# SD_CARD_REV2.net
KiCad netlist of a schematic drawn in Altium Designer
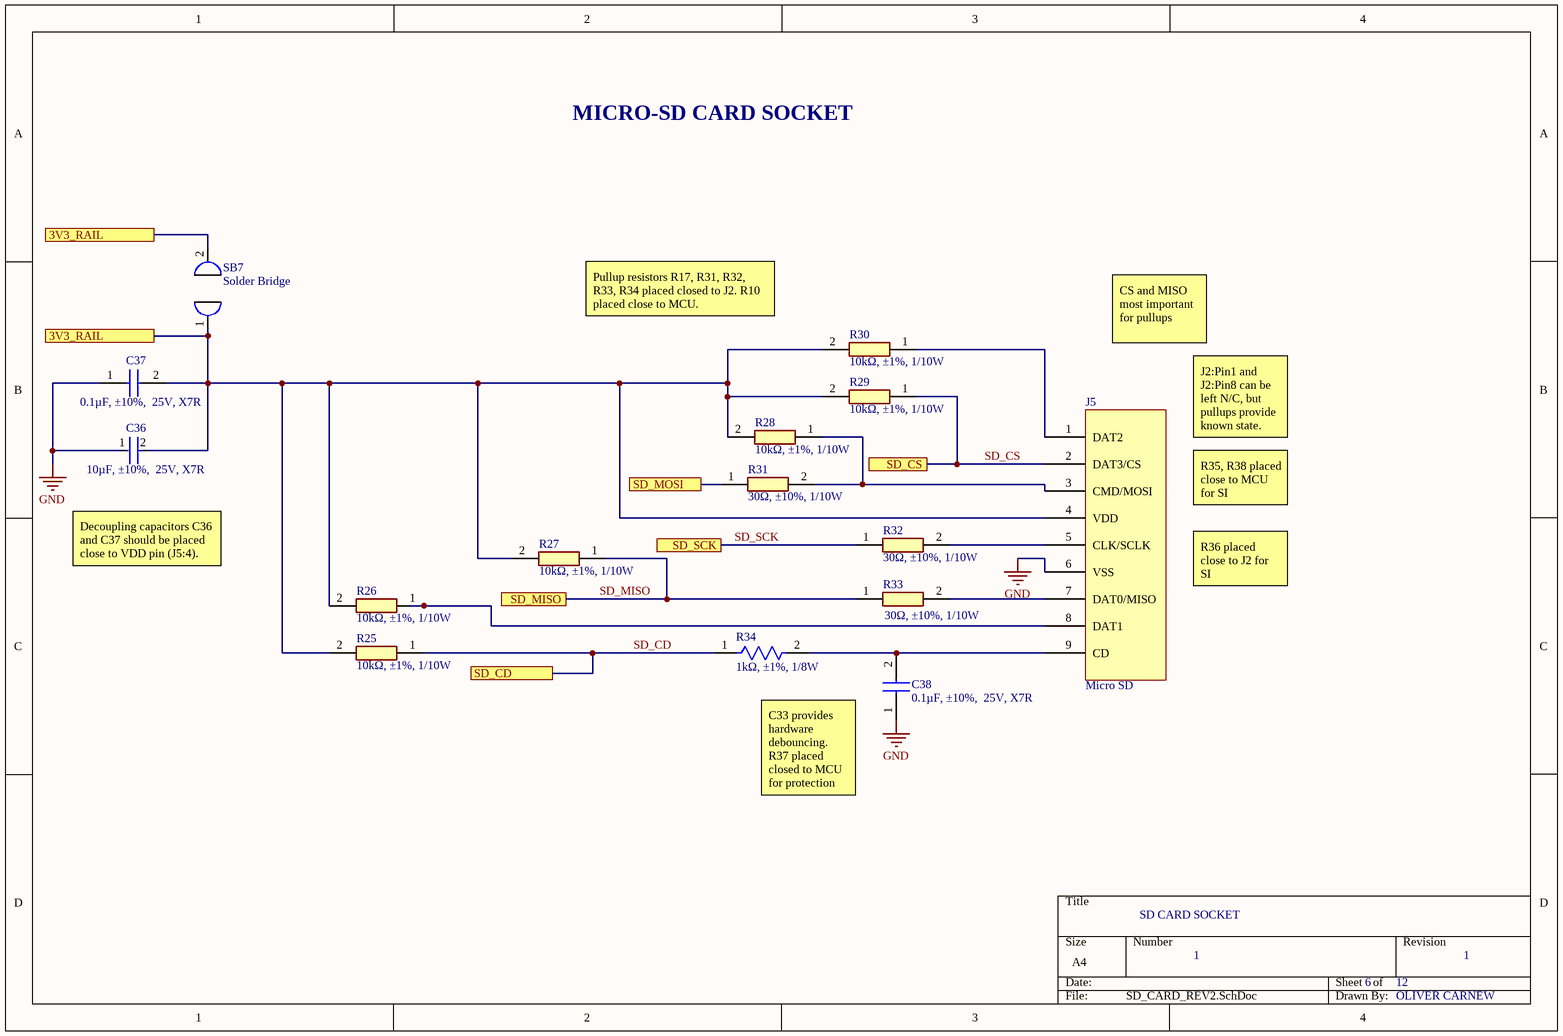
[diagram p0: SD_CARD_REV2.SchDoc]

(export (version "E")
  (design (tool "Eeschema 10.0.6"))
  (components
    (comp (ref "C36")
      (value "10µF, ±10%,  25V, X7R")
      (footprint "FP-CL21B106KOQNNNE-MFG")
      (description "CAP CER 10UF 16V X7R 0805 CL21B106KOQNNNE")
      (fields
        (field (name "MANUFACTURER PART NUMBER") "CL21B106KOQNNNE")
        (field (name "OCTOPART") "https://octopart.com/cl21b106koqnnne-samsung-19832289")
      )
      (libsource (lib "Altium Content Vault") (part "236180d848d6139a670b325ea6854c9"))
    )
    (comp (ref "C37")
      (value "0.1µF, ±10%,  25V, X7R")
      (footprint "SamacSys:CAPC1005X55N")
      (description "Capacitor CAP CER 0.1UF 25V X7R 0402 CL05B104KA5NNNC")
      (fields
        (field (name "MANUFACTURER_PART_NUMBER") "CL05B104KA5NNNC")
        (field (name "MOUSER PART NUMBER") "187-CL05B104KA5NNNC")
      )
      (libsource (lib "*") (part "CL05B104KA5NNNC"))
    )
    (comp (ref "C38")
      (value "0.1µF, ±10%,  25V, X7R")
      (footprint "SamacSys:CAPC1005X55N")
      (description "Capacitor CAP CER 0.1UF 25V X7R 0402 CL05B104KA5NNNC")
      (fields
        (field (name "MANUFACTURER_PART_NUMBER") "CL05B104KA5NNNC")
        (field (name "MOUSER PART NUMBER") "187-CL05B104KA5NNNC")
      )
      (libsource (lib "*") (part "CL05B104KA5NNNC"))
    )
    (comp (ref "J5")
      (value "Micro SD")
      (footprint "SD CARD")
      (description "ETSG")
      (libsource (lib "DANCE_LIB_REV2") (part "SD_CARD_MICRO"))
    )
    (comp (ref "R25")
      (value "10kΩ, ±1%, 1/10W")
      (footprint "SamacSys:RESC2012X60N")
      (description "Resistor RES 10K OHM 5% 1/8W 0805  RC0805JR-0710KL")
      (fields
        (field (name "MANUFACTURER_PART_NUMBER") "RC0805JR-0710KL")
        (field (name "MOUSER PART NUMBER") "603-RC0805JR-0710KL")
      )
      (libsource (lib "*") (part "RC0805JR-0710KL"))
    )
    (comp (ref "R26")
      (value "10kΩ, ±1%, 1/10W")
      (footprint "SamacSys:RESC2012X60N")
      (description "Resistor RES 10K OHM 5% 1/8W 0805  RC0805JR-0710KL")
      (fields
        (field (name "MANUFACTURER_PART_NUMBER") "RC0805JR-0710KL")
        (field (name "MOUSER PART NUMBER") "603-RC0805JR-0710KL")
      )
      (libsource (lib "*") (part "RC0805JR-0710KL"))
    )
    (comp (ref "R27")
      (value "10kΩ, ±1%, 1/10W")
      (footprint "SamacSys:RESC2012X60N")
      (description "Resistor RES 10K OHM 5% 1/8W 0805  RC0805JR-0710KL")
      (fields
        (field (name "MANUFACTURER_PART_NUMBER") "RC0805JR-0710KL")
        (field (name "MOUSER PART NUMBER") "603-RC0805JR-0710KL")
      )
      (libsource (lib "*") (part "RC0805JR-0710KL"))
    )
    (comp (ref "R28")
      (value "10kΩ, ±1%, 1/10W")
      (footprint "SamacSys:RESC2012X60N")
      (description "Resistor RES 10K OHM 5% 1/8W 0805  RC0805JR-0710KL")
      (fields
        (field (name "MANUFACTURER_PART_NUMBER") "RC0805JR-0710KL")
        (field (name "MOUSER PART NUMBER") "603-RC0805JR-0710KL")
      )
      (libsource (lib "*") (part "RC0805JR-0710KL"))
    )
    (comp (ref "R29")
      (value "10kΩ, ±1%, 1/10W")
      (footprint "SamacSys:RESC2012X60N")
      (description "Resistor RES 10K OHM 5% 1/8W 0805  RC0805JR-0710KL")
      (fields
        (field (name "MANUFACTURER_PART_NUMBER") "RC0805JR-0710KL")
        (field (name "MOUSER PART NUMBER") "603-RC0805JR-0710KL")
      )
      (libsource (lib "*") (part "RC0805JR-0710KL"))
    )
    (comp (ref "R30")
      (value "10kΩ, ±1%, 1/10W")
      (footprint "SamacSys:RESC2012X60N")
      (description "Resistor RES 10K OHM 5% 1/8W 0805  RC0805JR-0710KL")
      (fields
        (field (name "MANUFACTURER_PART_NUMBER") "RC0805JR-0710KL")
        (field (name "MOUSER PART NUMBER") "603-RC0805JR-0710KL")
      )
      (libsource (lib "*") (part "RC0805JR-0710KL"))
    )
    (comp (ref "R31")
      (value "30Ω, ±10%, 1/10W")
      (footprint "SamacSys:RESC1608X55N")
      (fields (field (name "MANUFACTURER_PART_NUMBER") "ERJPA3F30R0V"))
      (libsource (lib "*") (part "ERJPA3F30R0V"))
    )
    (comp (ref "R32")
      (value "30Ω, ±10%, 1/10W")
      (footprint "SamacSys:RESC1608X55N")
      (fields (field (name "MANUFACTURER_PART_NUMBER") "ERJPA3F30R0V"))
      (libsource (lib "*") (part "ERJPA3F30R0V"))
    )
    (comp (ref "R33")
      (value "30Ω, ±10%, 1/10W")
      (footprint "SamacSys:RESC1608X55N")
      (fields (field (name "MANUFACTURER_PART_NUMBER") "ERJPA3F30R0V"))
      (libsource (lib "*") (part "ERJPA3F30R0V"))
    )
    (comp (ref "R34")
      (value "1kΩ, ±1%, 1/8W")
      (footprint "FP-RNCP0603-IPC_A")
      (description "1kΩ ±1% 0.125W 0603 High Power Anti-Sulfur Thin Film Chip Resistor RNCP0603FTD1K00")
      (fields (field (name "TOLERANCE") "1%"))
      (libsource (lib "Altium Content Vault") (part "1029c3af85768c4190bb7ad29bc67b5"))
    )
    (comp (ref "SB7")
      (value "Solder Bridge")
      (footprint "SOLDER BRIDGE OPEN SMALL")
      (description "Tension Fill Solder Bridge")
      (libsource (lib "DANCE_LIB") (part "SOLDER_BRIDGE_TDROP"))
    )
  )
  (nets
    (net (code "1") (name "/3V3_RAIL") (class "Default")
      (node (ref "C36") (pin "2") (pinfunction "2_2") (pintype "passive"))
      (node (ref "C37") (pin "2") (pinfunction "2_2") (pintype "passive"))
      (node (ref "J5") (pin "4") (pinfunction "VDD_4") (pintype "passive"))
      (node (ref "R25") (pin "2") (pinfunction "2_2") (pintype "passive"))
      (node (ref "R26") (pin "2") (pinfunction "2_2") (pintype "passive"))
      (node (ref "R27") (pin "2") (pinfunction "2_2") (pintype "passive"))
      (node (ref "R28") (pin "2") (pinfunction "2_2") (pintype "passive"))
      (node (ref "R29") (pin "2") (pinfunction "2_2") (pintype "passive"))
      (node (ref "R30") (pin "2") (pinfunction "2_2") (pintype "passive"))
      (node (ref "SB7") (pin "1") (pinfunction "1_1") (pintype "passive"))
      (node (ref "SB7") (pin "2") (pinfunction "2_2") (pintype "passive"))
    )
    (net (code "2") (name "/SD_CD") (class "Default")
      (node (ref "R25") (pin "1") (pinfunction "1_1") (pintype "passive"))
      (node (ref "R34") (pin "1") (pinfunction "1_1") (pintype "passive"))
    )
    (net (code "3") (name "/SD_CS") (class "Default")
      (node (ref "J5") (pin "2") (pinfunction "DAT3/CS_2") (pintype "passive"))
      (node (ref "R29") (pin "1") (pinfunction "1_1") (pintype "passive"))
    )
    (net (code "4") (name "/SD_MISO") (class "Default")
      (node (ref "R27") (pin "1") (pinfunction "1_1") (pintype "passive"))
      (node (ref "R33") (pin "1") (pinfunction "1_1") (pintype "passive"))
    )
    (net (code "5") (name "/SD_MOSI") (class "Default")
      (node (ref "R31") (pin "1") (pinfunction "1_1") (pintype "passive"))
    )
    (net (code "6") (name "/SD_SCK") (class "Default")
      (node (ref "R32") (pin "1") (pinfunction "1_1") (pintype "passive"))
    )
    (net (code "7") (name "GND") (class "Default")
      (node (ref "C36") (pin "1") (pinfunction "1_1") (pintype "passive"))
      (node (ref "C37") (pin "1") (pinfunction "1_1") (pintype "passive"))
      (node (ref "C38") (pin "1") (pinfunction "1_1") (pintype "passive"))
      (node (ref "J5") (pin "6") (pinfunction "VSS_6") (pintype "passive"))
    )
    (net (code "8") (name "Net-(J5-CD)") (class "Default")
      (node (ref "C38") (pin "2") (pinfunction "2_2") (pintype "passive"))
      (node (ref "J5") (pin "9") (pinfunction "CD_9") (pintype "passive"))
      (node (ref "R34") (pin "2") (pinfunction "2_2") (pintype "passive"))
    )
    (net (code "9") (name "Net-(J5-CLK{slash}SCLK)") (class "Default")
      (node (ref "J5") (pin "5") (pinfunction "CLK/SCLK_5") (pintype "passive"))
      (node (ref "R32") (pin "2") (pinfunction "2_2") (pintype "passive"))
    )
    (net (code "10") (name "Net-(J5-CMD{slash}MOSI)") (class "Default")
      (node (ref "J5") (pin "3") (pinfunction "CMD/MOSI_3") (pintype "passive"))
      (node (ref "R28") (pin "1") (pinfunction "1_1") (pintype "passive"))
      (node (ref "R31") (pin "2") (pinfunction "2_2") (pintype "passive"))
    )
    (net (code "11") (name "Net-(J5-DAT0{slash}MISO)") (class "Default")
      (node (ref "J5") (pin "7") (pinfunction "DAT0/MISO_7") (pintype "passive"))
      (node (ref "R33") (pin "2") (pinfunction "2_2") (pintype "passive"))
    )
    (net (code "12") (name "Net-(J5-DAT1)") (class "Default")
      (node (ref "J5") (pin "8") (pinfunction "DAT1_8") (pintype "passive"))
      (node (ref "R26") (pin "1") (pinfunction "1_1") (pintype "passive"))
    )
    (net (code "13") (name "Net-(J5-DAT2)") (class "Default")
      (node (ref "J5") (pin "1") (pinfunction "DAT2_1") (pintype "passive"))
      (node (ref "R30") (pin "1") (pinfunction "1_1") (pintype "passive"))
    )
  )
)
